# LAUNCHXL-F28069_B_1400922_6.net
KiCad netlist of a schematic drawn in Altium Designer
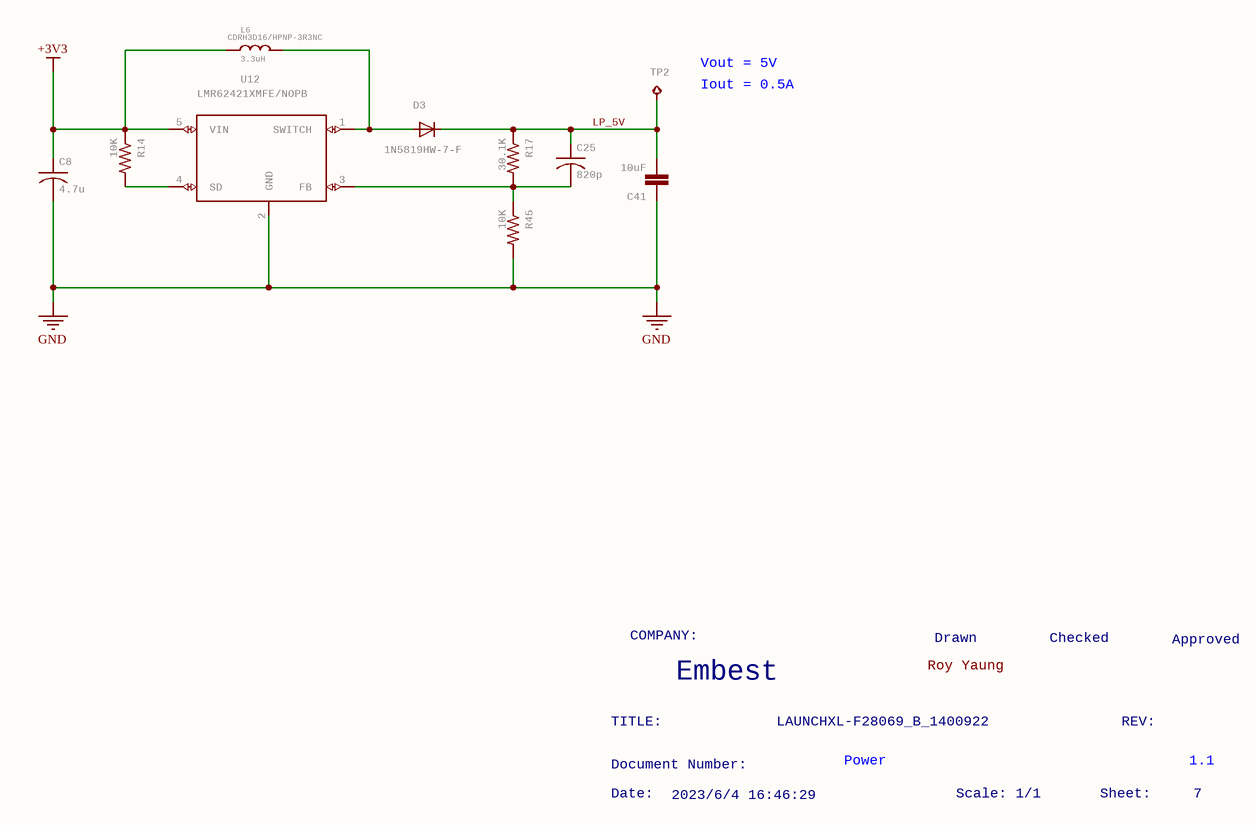
[diagram p0: LAUNCHXL-F28069_B_1400922_6.SchDoc]

(export (version "E")
  (design (tool "Eeschema 10.0.6"))
  (components
    (comp (ref "C8")
      (value "4.7u")
      (footprint "C0402")
      (description "CAPACITOR, American symbol")
      (libsource (lib "rcl") (part "C-USC0402"))
    )
    (comp (ref "C25")
      (value "820p")
      (footprint "C0402")
      (description "CAPACITOR, American symbol")
      (libsource (lib "rcl") (part "C-USC0402"))
    )
    (comp (ref "C41")
      (value "10uF")
      (footprint "SPARKFUN_1210")
      (description "CapacitorStandard 0603 ceramic capacitor, and 0.1\" leaded capacitor.")
      (fields (field (name "LIBRARYNAME") "RF430FRL152H_EVM_a"))
      (libsource (lib "RF430FRL152H_EVM_a") (part "SPARKFUN_CAP1210"))
    )
    (comp (ref "D3")
      (value "1N5819HW-7-F")
      (footprint "SOD123")
      (description "DIODE   high speed (Philips)")
      (libsource (lib "diode") (part "1N4148"))
    )
    (comp (ref "L6")
      (value "3.3uH")
      (footprint "INDUCT-3_7*3_5")
      (libsource (lib "LAUNCHXL-F28027") (part "VLF4012A"))
    )
    (comp (ref "R14")
      (value "10K")
      (footprint "R0402")
      (description "RESISTOR, American symbol")
      (libsource (lib "rcl") (part "R-US_R0402"))
    )
    (comp (ref "R17")
      (value "30.1K")
      (footprint "R0402")
      (description "RESISTOR, American symbol")
      (libsource (lib "rcl") (part "R-US_R0402"))
    )
    (comp (ref "R45")
      (value "10K")
      (footprint "R0402")
      (description "RESISTOR, American symbol")
      (libsource (lib "rcl") (part "R-US_R0402"))
    )
    (comp (ref "TP2")
      (value "TESTPAD_TPB1,27")
      (footprint "TESTPAD_B1,27")
      (description "Test pad")
      (fields (field (name "LIBRARYNAME") "RF430FRL152H_EVM_a"))
      (libsource (lib "RF430FRL152H_EVM_a") (part "TESTPAD_TPB1,27"))
    )
    (comp (ref "U12")
      (value "LMR62421XMFE/NOPB")
      (footprint "SOT23-5-DBV")
      (libsource (lib "LAUNCHXL-F28027") (part "LMR62421XMFE/NOPB"))
    )
  )
  (nets
    (net (code "1") (name "+3V3") (class "Default")
      (node (ref "C8") (pin "1") (pinfunction "1_1") (pintype "passive"))
      (node (ref "L6") (pin "P$1") (pinfunction "1_P$1") (pintype "bidirectional"))
      (node (ref "R14") (pin "1") (pinfunction "1_1") (pintype "passive"))
      (node (ref "U12") (pin "5") (pinfunction "VIN_5") (pintype "bidirectional"))
    )
    (net (code "2") (name "/LP_5V") (class "Default")
      (node (ref "C25") (pin "1") (pinfunction "1_1") (pintype "passive"))
      (node (ref "C41") (pin "2") (pinfunction "2_2") (pintype "passive"))
      (node (ref "D3") (pin "C") (pinfunction "C_C") (pintype "passive"))
      (node (ref "R17") (pin "1") (pinfunction "1_1") (pintype "passive"))
      (node (ref "TP2") (pin "TP") (pinfunction "TP_TP") (pintype "input"))
    )
    (net (code "3") (name "GND") (class "Default")
      (node (ref "C41") (pin "1") (pinfunction "1_1") (pintype "passive"))
      (node (ref "C8") (pin "2") (pinfunction "2_2") (pintype "passive"))
      (node (ref "R45") (pin "2") (pinfunction "2_2") (pintype "passive"))
      (node (ref "U12") (pin "2") (pinfunction "GND_2") (pintype "bidirectional"))
    )
    (net (code "4") (name "Net-(L6-2)") (class "Default")
      (node (ref "D3") (pin "A") (pinfunction "A_A") (pintype "passive"))
      (node (ref "L6") (pin "P$2") (pinfunction "2_P$2") (pintype "bidirectional"))
      (node (ref "U12") (pin "1") (pinfunction "SWITCH_1") (pintype "bidirectional"))
    )
    (net (code "5") (name "Net-(U12-FB)") (class "Default")
      (node (ref "C25") (pin "2") (pinfunction "2_2") (pintype "passive"))
      (node (ref "R17") (pin "2") (pinfunction "2_2") (pintype "passive"))
      (node (ref "R45") (pin "1") (pinfunction "1_1") (pintype "passive"))
      (node (ref "U12") (pin "3") (pinfunction "FB_3") (pintype "bidirectional"))
    )
    (net (code "6") (name "Net-(U12-SD)") (class "Default")
      (node (ref "R14") (pin "2") (pinfunction "2_2") (pintype "passive"))
      (node (ref "U12") (pin "4") (pinfunction "SD_4") (pintype "bidirectional"))
    )
  )
)
